# 04_ControllerStage_v1.net
KiCad netlist of a schematic drawn in EAGLE
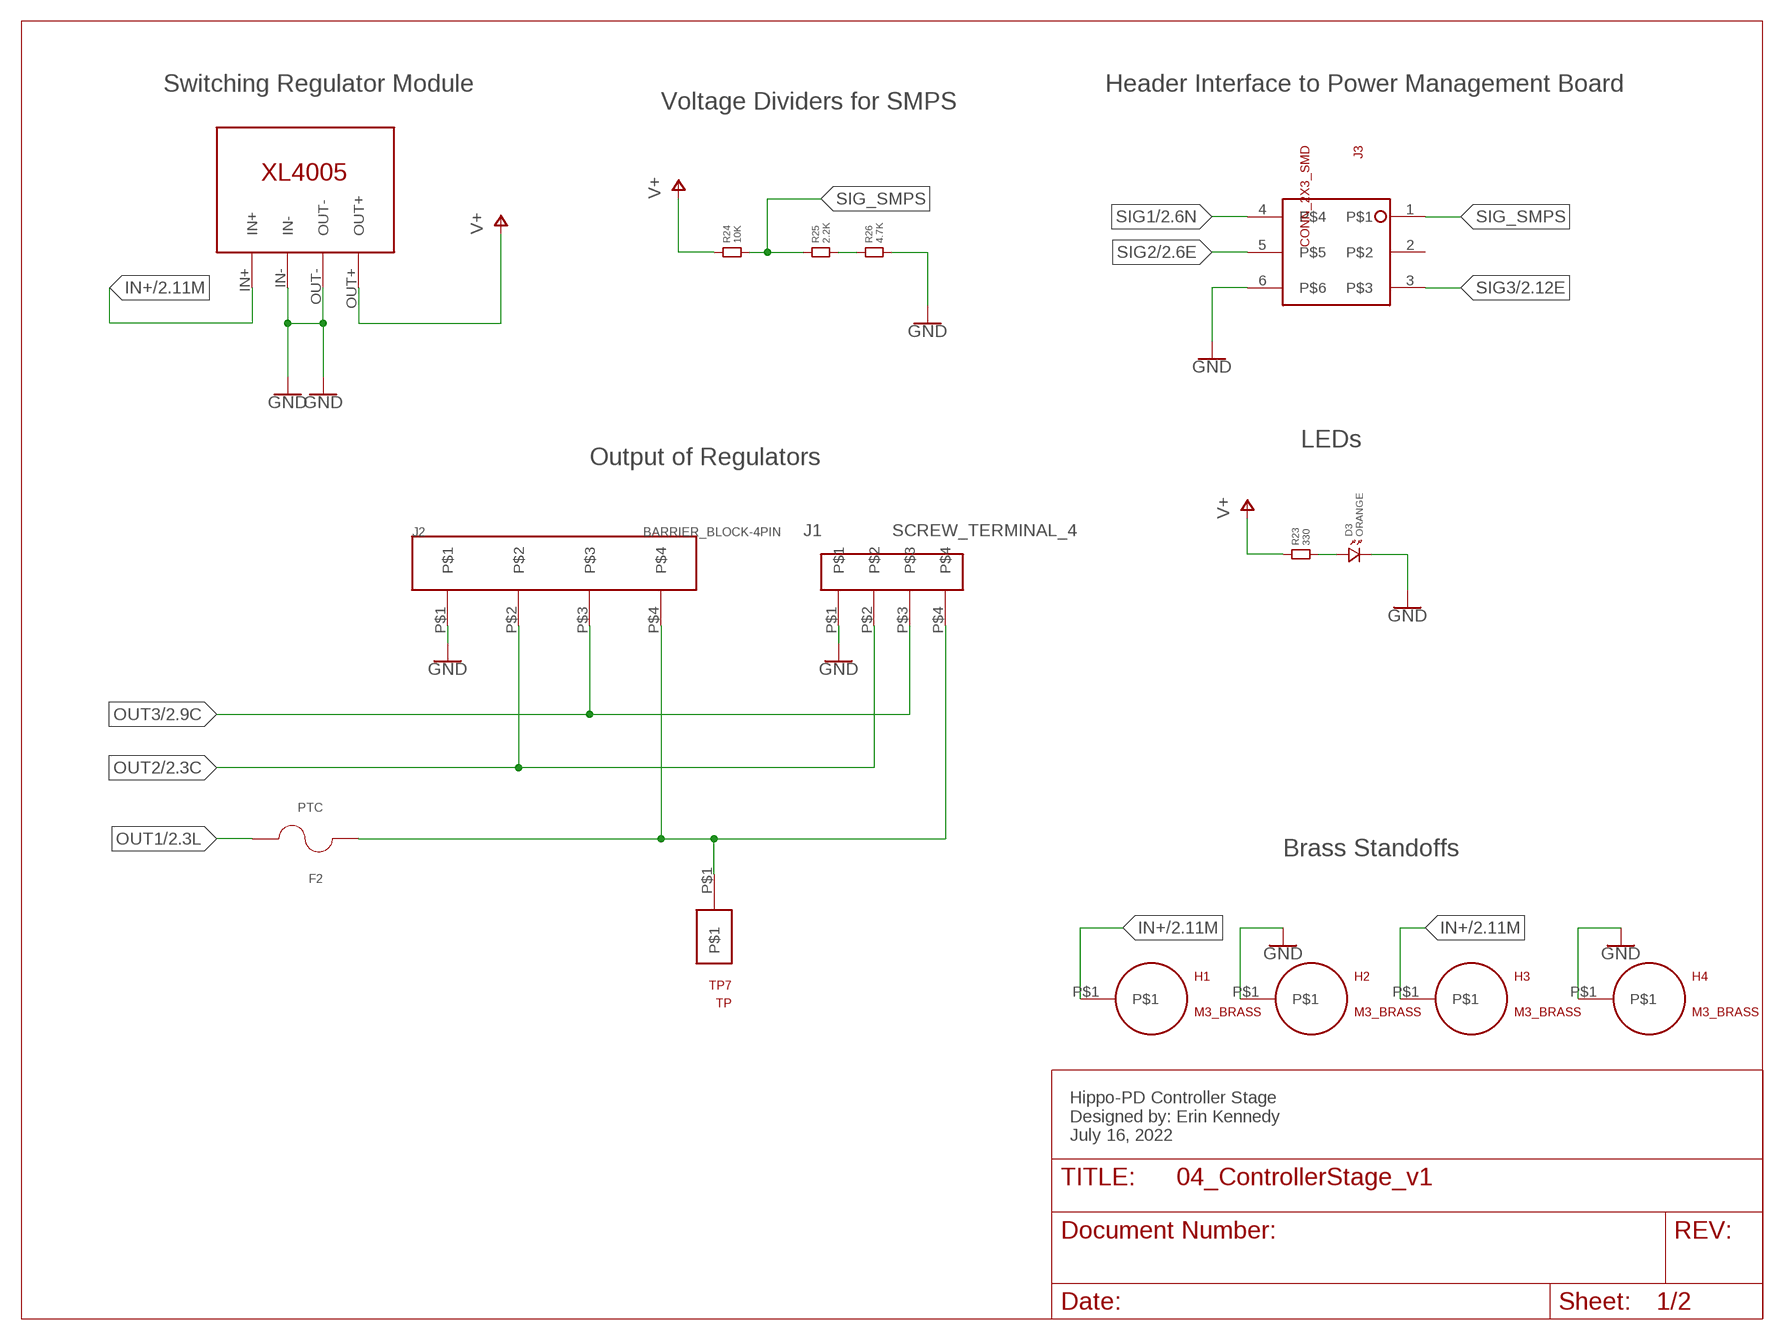
[diagram p0: schematic, sheet 1]
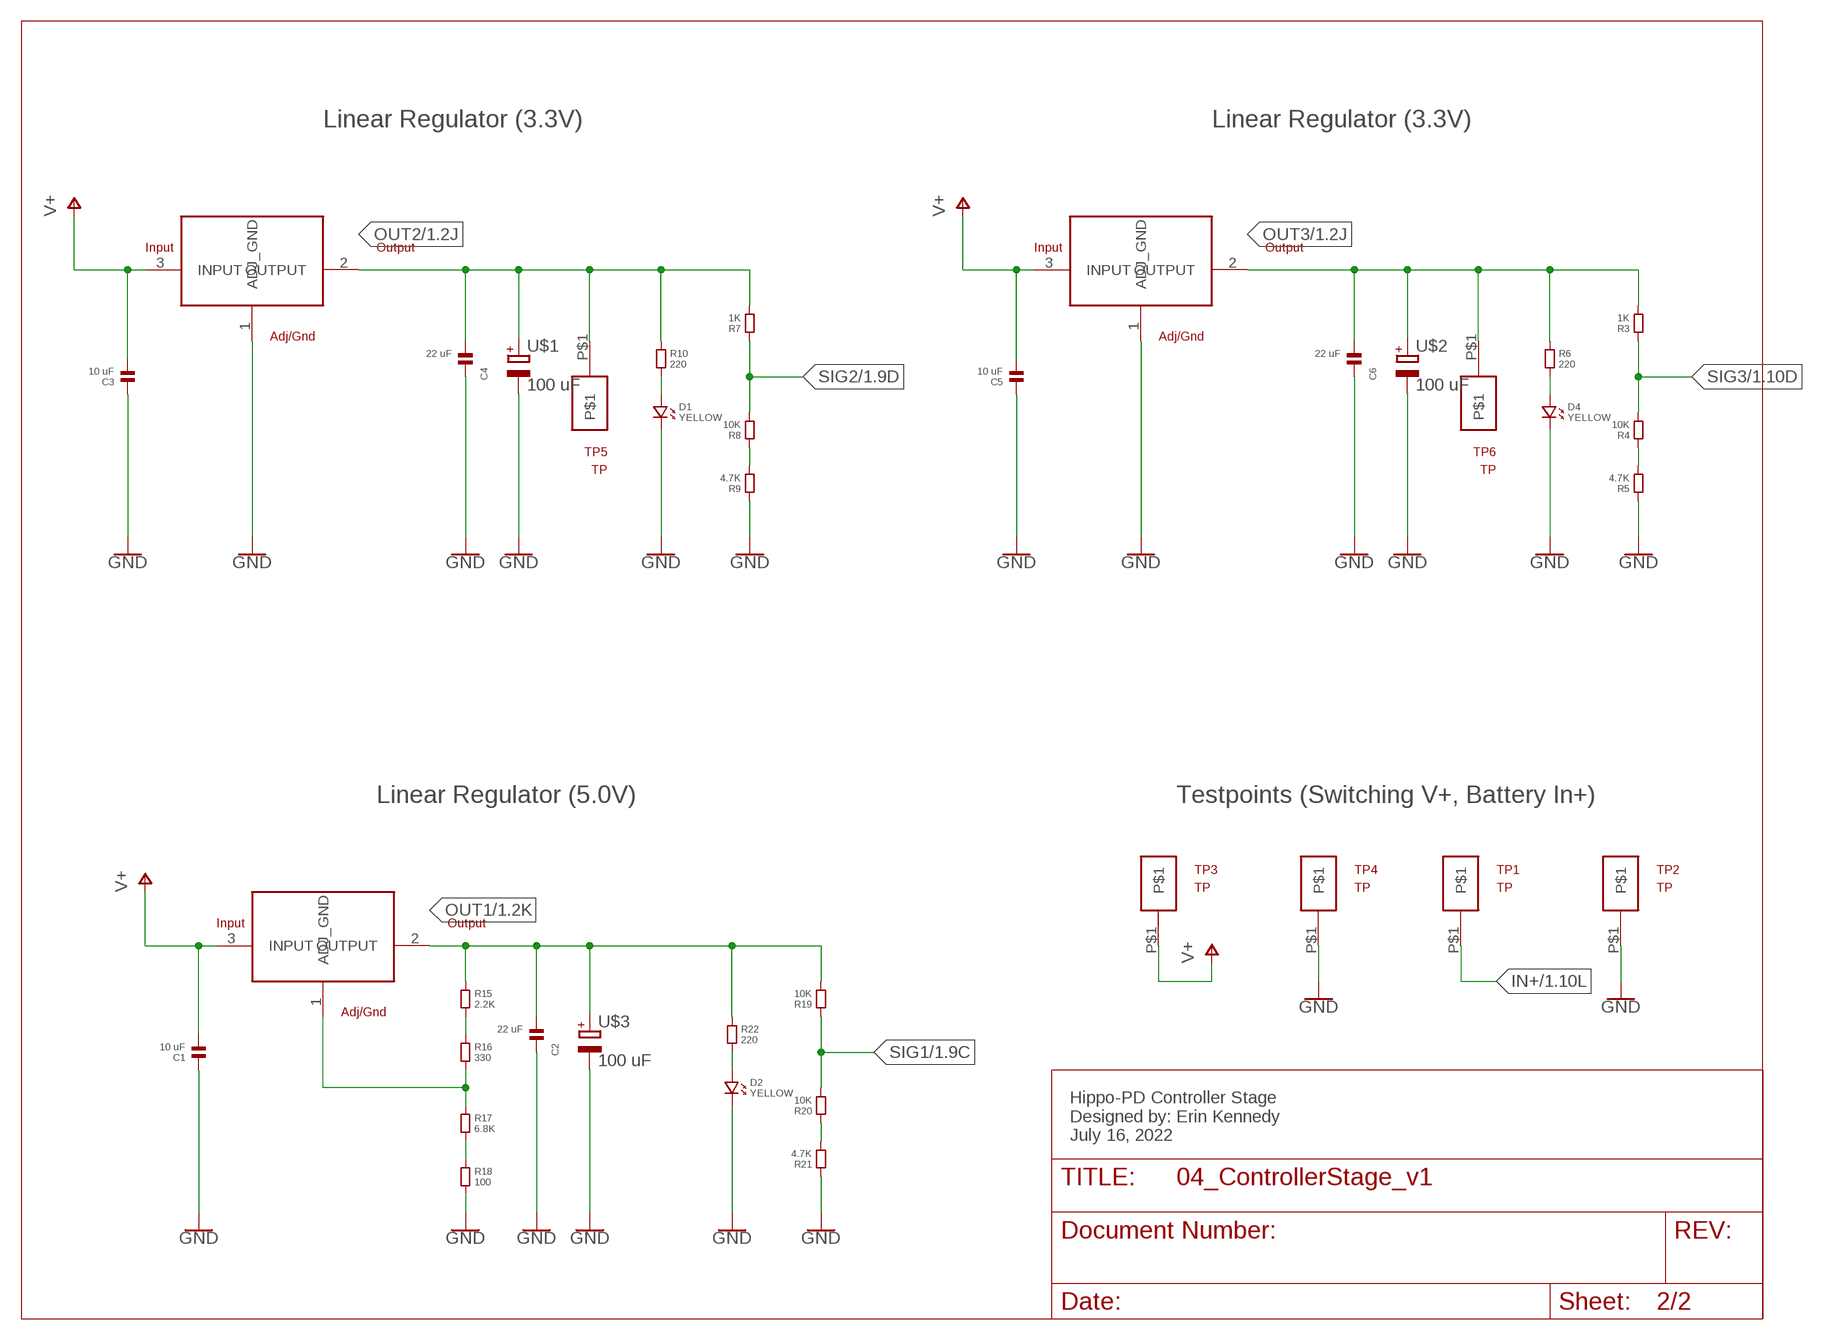
[diagram p1: schematic, sheet 2]

(export (version "E")
  (design (tool "Eeschema 10.0.6"))
  (components
    (comp (ref "C1")
      (value "10 uF")
      (footprint "eagle-import:1206")
      (libsource (lib "eagle-import") (part "CAPACITOR.1206"))
    )
    (comp (ref "C2")
      (value "22 uF")
      (footprint "eagle-import:1206")
      (libsource (lib "eagle-import") (part "CAPACITOR.1206"))
    )
    (comp (ref "C3")
      (value "10 uF")
      (footprint "eagle-import:1206")
      (libsource (lib "eagle-import") (part "CAPACITOR.1206"))
    )
    (comp (ref "C4")
      (value "22 uF")
      (footprint "eagle-import:1206")
      (libsource (lib "eagle-import") (part "CAPACITOR.1206"))
    )
    (comp (ref "C5")
      (value "10 uF")
      (footprint "eagle-import:1206")
      (libsource (lib "eagle-import") (part "CAPACITOR.1206"))
    )
    (comp (ref "C6")
      (value "22 uF")
      (footprint "eagle-import:1206")
      (libsource (lib "eagle-import") (part "CAPACITOR.1206"))
    )
    (comp (ref "D1")
      (value "YELLOW")
      (footprint "eagle-import:1206.LED")
      (libsource (lib "eagle-import") (part "LED.1206"))
    )
    (comp (ref "D2")
      (value "YELLOW")
      (footprint "eagle-import:1206.LED")
      (libsource (lib "eagle-import") (part "LED.1206"))
    )
    (comp (ref "D4")
      (value "YELLOW")
      (footprint "eagle-import:1206.LED")
      (libsource (lib "eagle-import") (part "LED.1206"))
    )
    (comp (ref "R1")
      (value "AZ1117CDAZ1117CD")
      (footprint "eagle-import:AZ1117CD")
      (libsource (lib "eagle-import") (part "AZ1117CDAZ1117CD"))
    )
    (comp (ref "R2")
      (value "AZ1117CDAZ1117CD")
      (footprint "eagle-import:AZ1117CD")
      (libsource (lib "eagle-import") (part "AZ1117CDAZ1117CD"))
    )
    (comp (ref "R3")
      (value "1K")
      (footprint "eagle-import:1206")
      (libsource (lib "eagle-import") (part "RESISTOR.1206"))
    )
    (comp (ref "R4")
      (value "10K")
      (footprint "eagle-import:1206")
      (libsource (lib "eagle-import") (part "RESISTOR.1206"))
    )
    (comp (ref "R5")
      (value "4.7K")
      (footprint "eagle-import:1206")
      (libsource (lib "eagle-import") (part "RESISTOR.1206"))
    )
    (comp (ref "R6")
      (value "220")
      (footprint "eagle-import:1206")
      (libsource (lib "eagle-import") (part "RESISTOR.1206"))
    )
    (comp (ref "R7")
      (value "1K")
      (footprint "eagle-import:1206")
      (libsource (lib "eagle-import") (part "RESISTOR.1206"))
    )
    (comp (ref "R8")
      (value "10K")
      (footprint "eagle-import:1206")
      (libsource (lib "eagle-import") (part "RESISTOR.1206"))
    )
    (comp (ref "R9")
      (value "4.7K")
      (footprint "eagle-import:1206")
      (libsource (lib "eagle-import") (part "RESISTOR.1206"))
    )
    (comp (ref "R10")
      (value "220")
      (footprint "eagle-import:1206")
      (libsource (lib "eagle-import") (part "RESISTOR.1206"))
    )
    (comp (ref "R14")
      (value "AZ1084C")
      (footprint "eagle-import:AZ1084C")
      (libsource (lib "eagle-import") (part "AZ1084C"))
    )
    (comp (ref "R15")
      (value "2.2K")
      (footprint "eagle-import:1206")
      (libsource (lib "eagle-import") (part "RESISTOR.1206"))
    )
    (comp (ref "R16")
      (value "330")
      (footprint "eagle-import:1206")
      (libsource (lib "eagle-import") (part "RESISTOR.1206"))
    )
    (comp (ref "R17")
      (value "6.8K")
      (footprint "eagle-import:1206")
      (libsource (lib "eagle-import") (part "RESISTOR.1206"))
    )
    (comp (ref "R18")
      (value "100")
      (footprint "eagle-import:1206")
      (libsource (lib "eagle-import") (part "RESISTOR.1206"))
    )
    (comp (ref "R19")
      (value "10K")
      (footprint "eagle-import:1206")
      (libsource (lib "eagle-import") (part "RESISTOR.1206"))
    )
    (comp (ref "R20")
      (value "10K")
      (footprint "eagle-import:1206")
      (libsource (lib "eagle-import") (part "RESISTOR.1206"))
    )
    (comp (ref "R21")
      (value "4.7K")
      (footprint "eagle-import:1206")
      (libsource (lib "eagle-import") (part "RESISTOR.1206"))
    )
    (comp (ref "R22")
      (value "220")
      (footprint "eagle-import:1206")
      (libsource (lib "eagle-import") (part "RESISTOR.1206"))
    )
    (comp (ref "TP1") (value "TP") (footprint "eagle-import:TP") (libsource (lib "eagle-import") (part "TP")))
    (comp (ref "TP2") (value "TP") (footprint "eagle-import:TP") (libsource (lib "eagle-import") (part "TP")))
    (comp (ref "TP3") (value "TP") (footprint "eagle-import:TP") (libsource (lib "eagle-import") (part "TP")))
    (comp (ref "TP4") (value "TP") (footprint "eagle-import:TP") (libsource (lib "eagle-import") (part "TP")))
    (comp (ref "TP5") (value "TP") (footprint "eagle-import:TP") (libsource (lib "eagle-import") (part "TP")))
    (comp (ref "TP6") (value "TP") (footprint "eagle-import:TP") (libsource (lib "eagle-import") (part "TP")))
    (comp (ref "U$1")
      (value "100 uF")
      (footprint "eagle-import:ELECTROLYTIC_CAP")
      (fields (field (name "MF") "Wurth Electronics") (field (name "MP") "865080545012"))
      (libsource (lib "eagle-import") (part "ELECTROLYTIC_CAP"))
    )
    (comp (ref "U$2")
      (value "100 uF")
      (footprint "eagle-import:ELECTROLYTIC_CAP")
      (fields (field (name "MF") "Wurth Electronics") (field (name "MP") "865080545012"))
      (libsource (lib "eagle-import") (part "ELECTROLYTIC_CAP"))
    )
    (comp (ref "U$3")
      (value "100 uF")
      (footprint "eagle-import:ELECTROLYTIC_CAP")
      (fields (field (name "MF") "Wurth Electronics") (field (name "MP") "865080545012"))
      (libsource (lib "eagle-import") (part "ELECTROLYTIC_CAP"))
    )
    (comp (ref "D3")
      (value "ORANGE")
      (footprint "eagle-import:1206.LED")
      (libsource (lib "eagle-import") (part "LED.1206"))
    )
    (comp (ref "F2")
      (value "PTC")
      (footprint "eagle-import:PTC")
      (fields (field (name "MF") "Bel Fuse") (field (name "MP") "0ZCF0075AF2C"))
      (libsource (lib "eagle-import") (part "PTC"))
    )
    (comp (ref "H1")
      (value "M3_BRASS")
      (footprint "eagle-import:M3_BRASS")
      (libsource (lib "eagle-import") (part "M3_BRASS"))
    )
    (comp (ref "H2")
      (value "M3_BRASS")
      (footprint "eagle-import:M3_BRASS")
      (libsource (lib "eagle-import") (part "M3_BRASS"))
    )
    (comp (ref "H3")
      (value "M3_BRASS")
      (footprint "eagle-import:M3_BRASS")
      (libsource (lib "eagle-import") (part "M3_BRASS"))
    )
    (comp (ref "H4")
      (value "M3_BRASS")
      (footprint "eagle-import:M3_BRASS")
      (libsource (lib "eagle-import") (part "M3_BRASS"))
    )
    (comp (ref "J1")
      (value "SCREW_TERMINAL_4")
      (footprint "eagle-import:SCREW_TERM_4")
      (libsource (lib "eagle-import") (part "SCREW_TERMINAL_4"))
    )
    (comp (ref "J2")
      (value "BARRIER_BLOCK-4PIN")
      (footprint "eagle-import:BARRIERBLOCK-4PIN")
      (libsource (lib "eagle-import") (part "BARRIER_BLOCK-4PIN"))
    )
    (comp (ref "J3")
      (value "CONN_2X3_SMD")
      (footprint "eagle-import:2X3_SMD_CONNECTOR")
      (libsource (lib "eagle-import") (part "CONN_2X3_SMD"))
    )
    (comp (ref "R23")
      (value "330")
      (footprint "eagle-import:1206")
      (libsource (lib "eagle-import") (part "RESISTOR.1206"))
    )
    (comp (ref "R24")
      (value "10K")
      (footprint "eagle-import:1206")
      (libsource (lib "eagle-import") (part "RESISTOR.1206"))
    )
    (comp (ref "R25")
      (value "2.2K")
      (footprint "eagle-import:1206")
      (libsource (lib "eagle-import") (part "RESISTOR.1206"))
    )
    (comp (ref "R26")
      (value "4.7K")
      (footprint "eagle-import:1206")
      (libsource (lib "eagle-import") (part "RESISTOR.1206"))
    )
    (comp (ref "TP7") (value "TP") (footprint "eagle-import:TP") (libsource (lib "eagle-import") (part "TP")))
    (comp (ref "U1")
      (value "XL4005-DEV")
      (footprint "eagle-import:XL4005-DEV")
      (libsource (lib "eagle-import") (part "XL4005-DEV"))
    )
  )
  (nets
    (net (code "1") (name "GND") (class "Default")
      (node (ref "C1") (pin "1") (pinfunction "1_1") (pintype "bidirectional"))
      (node (ref "C2") (pin "1") (pinfunction "1_1") (pintype "bidirectional"))
      (node (ref "C3") (pin "1") (pinfunction "1_1") (pintype "bidirectional"))
      (node (ref "C4") (pin "1") (pinfunction "1_1") (pintype "bidirectional"))
      (node (ref "C5") (pin "1") (pinfunction "1_1") (pintype "bidirectional"))
      (node (ref "C6") (pin "1") (pinfunction "1_1") (pintype "bidirectional"))
      (node (ref "D1") (pin "P$2") (pinfunction "2_P$2") (pintype "bidirectional"))
      (node (ref "D2") (pin "P$2") (pinfunction "2_P$2") (pintype "bidirectional"))
      (node (ref "D3") (pin "P$2") (pinfunction "2_P$2") (pintype "bidirectional"))
      (node (ref "D4") (pin "P$2") (pinfunction "2_P$2") (pintype "bidirectional"))
      (node (ref "H2") (pin "P$1") (pinfunction "P$1_P$1") (pintype "bidirectional"))
      (node (ref "H4") (pin "P$1") (pinfunction "P$1_P$1") (pintype "bidirectional"))
      (node (ref "J1") (pin "P$1") (pinfunction "P$1_P$1") (pintype "bidirectional"))
      (node (ref "J2") (pin "P$1") (pinfunction "P$1_P$1") (pintype "bidirectional"))
      (node (ref "J3") (pin "6") (pinfunction "P$6_6") (pintype "bidirectional"))
      (node (ref "R1") (pin "1") (pinfunction "ADJ_GND_1") (pintype "bidirectional"))
      (node (ref "R18") (pin "2") (pinfunction "2_2") (pintype "bidirectional"))
      (node (ref "R2") (pin "1") (pinfunction "ADJ_GND_1") (pintype "bidirectional"))
      (node (ref "R21") (pin "1") (pinfunction "1_1") (pintype "bidirectional"))
      (node (ref "R26") (pin "2") (pinfunction "2_2") (pintype "bidirectional"))
      (node (ref "R5") (pin "1") (pinfunction "1_1") (pintype "bidirectional"))
      (node (ref "R9") (pin "1") (pinfunction "1_1") (pintype "bidirectional"))
      (node (ref "TP2") (pin "P$1") (pinfunction "P$1_P$1") (pintype "bidirectional"))
      (node (ref "TP4") (pin "P$1") (pinfunction "P$1_P$1") (pintype "bidirectional"))
      (node (ref "U$1") (pin "-") (pinfunction "-_-") (pintype "passive"))
      (node (ref "U$2") (pin "-") (pinfunction "-_-") (pintype "passive"))
      (node (ref "U$3") (pin "-") (pinfunction "-_-") (pintype "passive"))
      (node (ref "U1") (pin "IN-") (pinfunction "IN-_IN-") (pintype "bidirectional"))
      (node (ref "U1") (pin "OUT-") (pinfunction "OUT-_OUT-") (pintype "bidirectional"))
    )
    (net (code "2") (name "IN+") (class "Default")
      (node (ref "H1") (pin "P$1") (pinfunction "P$1_P$1") (pintype "bidirectional"))
      (node (ref "H3") (pin "P$1") (pinfunction "P$1_P$1") (pintype "bidirectional"))
      (node (ref "TP1") (pin "P$1") (pinfunction "P$1_P$1") (pintype "bidirectional"))
      (node (ref "U1") (pin "IN+") (pinfunction "IN+_IN+") (pintype "bidirectional"))
    )
    (net (code "3") (name "Net-(D1-1)") (class "Default")
      (node (ref "D1") (pin "P$1") (pinfunction "1_P$1") (pintype "bidirectional"))
      (node (ref "R10") (pin "2") (pinfunction "2_2") (pintype "bidirectional"))
    )
    (net (code "4") (name "Net-(D2-1)") (class "Default")
      (node (ref "D2") (pin "P$1") (pinfunction "1_P$1") (pintype "bidirectional"))
      (node (ref "R22") (pin "2") (pinfunction "2_2") (pintype "bidirectional"))
    )
    (net (code "5") (name "Net-(D3-1)") (class "Default")
      (node (ref "D3") (pin "P$1") (pinfunction "1_P$1") (pintype "bidirectional"))
      (node (ref "R23") (pin "2") (pinfunction "2_2") (pintype "bidirectional"))
    )
    (net (code "6") (name "Net-(D4-1)") (class "Default")
      (node (ref "D4") (pin "P$1") (pinfunction "1_P$1") (pintype "bidirectional"))
      (node (ref "R6") (pin "2") (pinfunction "2_2") (pintype "bidirectional"))
    )
    (net (code "7") (name "Net-(F2-Pad1)") (class "Default")
      (node (ref "F2") (pin "1") (pinfunction "1_1") (pintype "passive"))
      (node (ref "J1") (pin "P$4") (pinfunction "P$4_P$4") (pintype "bidirectional"))
      (node (ref "J2") (pin "P$4") (pinfunction "P$4_P$4") (pintype "bidirectional"))
      (node (ref "TP7") (pin "P$1") (pinfunction "P$1_P$1") (pintype "bidirectional"))
    )
    (net (code "8") (name "Net-(R4-Pad1)") (class "Default")
      (node (ref "R4") (pin "1") (pinfunction "1_1") (pintype "bidirectional"))
      (node (ref "R5") (pin "2") (pinfunction "2_2") (pintype "bidirectional"))
    )
    (net (code "9") (name "Net-(R8-Pad1)") (class "Default")
      (node (ref "R8") (pin "1") (pinfunction "1_1") (pintype "bidirectional"))
      (node (ref "R9") (pin "2") (pinfunction "2_2") (pintype "bidirectional"))
    )
    (net (code "10") (name "Net-(R14-ADJ_GND)") (class "Default")
      (node (ref "R14") (pin "1") (pinfunction "ADJ_GND_1") (pintype "bidirectional"))
      (node (ref "R16") (pin "2") (pinfunction "2_2") (pintype "bidirectional"))
      (node (ref "R17") (pin "1") (pinfunction "1_1") (pintype "bidirectional"))
    )
    (net (code "11") (name "Net-(R15-Pad2)") (class "Default")
      (node (ref "R15") (pin "2") (pinfunction "2_2") (pintype "bidirectional"))
      (node (ref "R16") (pin "1") (pinfunction "1_1") (pintype "bidirectional"))
    )
    (net (code "12") (name "Net-(R17-Pad2)") (class "Default")
      (node (ref "R17") (pin "2") (pinfunction "2_2") (pintype "bidirectional"))
      (node (ref "R18") (pin "1") (pinfunction "1_1") (pintype "bidirectional"))
    )
    (net (code "13") (name "Net-(R20-Pad1)") (class "Default")
      (node (ref "R20") (pin "1") (pinfunction "1_1") (pintype "bidirectional"))
      (node (ref "R21") (pin "2") (pinfunction "2_2") (pintype "bidirectional"))
    )
    (net (code "14") (name "Net-(R25-Pad2)") (class "Default")
      (node (ref "R25") (pin "2") (pinfunction "2_2") (pintype "bidirectional"))
      (node (ref "R26") (pin "1") (pinfunction "1_1") (pintype "bidirectional"))
    )
    (net (code "15") (name "OUT1") (class "Default")
      (node (ref "C2") (pin "2") (pinfunction "2_2") (pintype "bidirectional"))
      (node (ref "F2") (pin "2") (pinfunction "2_2") (pintype "passive"))
      (node (ref "R14") (pin "2") (pinfunction "OUTPUT_2") (pintype "bidirectional"))
      (node (ref "R15") (pin "1") (pinfunction "1_1") (pintype "bidirectional"))
      (node (ref "R19") (pin "2") (pinfunction "2_2") (pintype "bidirectional"))
      (node (ref "R22") (pin "1") (pinfunction "1_1") (pintype "bidirectional"))
      (node (ref "U$3") (pin "+") (pinfunction "+_+") (pintype "passive"))
    )
    (net (code "16") (name "OUT2") (class "Default")
      (node (ref "C4") (pin "2") (pinfunction "2_2") (pintype "bidirectional"))
      (node (ref "J1") (pin "P$2") (pinfunction "P$2_P$2") (pintype "bidirectional"))
      (node (ref "J2") (pin "P$2") (pinfunction "P$2_P$2") (pintype "bidirectional"))
      (node (ref "R1") (pin "2") (pinfunction "OUTPUT_2") (pintype "bidirectional"))
      (node (ref "R10") (pin "1") (pinfunction "1_1") (pintype "bidirectional"))
      (node (ref "R7") (pin "2") (pinfunction "2_2") (pintype "bidirectional"))
      (node (ref "TP5") (pin "P$1") (pinfunction "P$1_P$1") (pintype "bidirectional"))
      (node (ref "U$1") (pin "+") (pinfunction "+_+") (pintype "passive"))
    )
    (net (code "17") (name "OUT3") (class "Default")
      (node (ref "C6") (pin "2") (pinfunction "2_2") (pintype "bidirectional"))
      (node (ref "J1") (pin "P$3") (pinfunction "P$3_P$3") (pintype "bidirectional"))
      (node (ref "J2") (pin "P$3") (pinfunction "P$3_P$3") (pintype "bidirectional"))
      (node (ref "R2") (pin "2") (pinfunction "OUTPUT_2") (pintype "bidirectional"))
      (node (ref "R3") (pin "2") (pinfunction "2_2") (pintype "bidirectional"))
      (node (ref "R6") (pin "1") (pinfunction "1_1") (pintype "bidirectional"))
      (node (ref "TP6") (pin "P$1") (pinfunction "P$1_P$1") (pintype "bidirectional"))
      (node (ref "U$2") (pin "+") (pinfunction "+_+") (pintype "passive"))
    )
    (net (code "18") (name "SIG1") (class "Default")
      (node (ref "J3") (pin "4") (pinfunction "P$4_4") (pintype "bidirectional"))
      (node (ref "R19") (pin "1") (pinfunction "1_1") (pintype "bidirectional"))
      (node (ref "R20") (pin "2") (pinfunction "2_2") (pintype "bidirectional"))
    )
    (net (code "19") (name "SIG2") (class "Default")
      (node (ref "J3") (pin "5") (pinfunction "P$5_5") (pintype "bidirectional"))
      (node (ref "R7") (pin "1") (pinfunction "1_1") (pintype "bidirectional"))
      (node (ref "R8") (pin "2") (pinfunction "2_2") (pintype "bidirectional"))
    )
    (net (code "20") (name "SIG3") (class "Default")
      (node (ref "J3") (pin "3") (pinfunction "P$3_3") (pintype "bidirectional"))
      (node (ref "R3") (pin "1") (pinfunction "1_1") (pintype "bidirectional"))
      (node (ref "R4") (pin "2") (pinfunction "2_2") (pintype "bidirectional"))
    )
    (net (code "21") (name "SIG_SMPS") (class "Default")
      (node (ref "J3") (pin "1") (pinfunction "P$1_1") (pintype "bidirectional"))
      (node (ref "R24") (pin "2") (pinfunction "2_2") (pintype "bidirectional"))
      (node (ref "R25") (pin "1") (pinfunction "1_1") (pintype "bidirectional"))
    )
    (net (code "22") (name "V+") (class "Default")
      (node (ref "C1") (pin "2") (pinfunction "2_2") (pintype "bidirectional"))
      (node (ref "C3") (pin "2") (pinfunction "2_2") (pintype "bidirectional"))
      (node (ref "C5") (pin "2") (pinfunction "2_2") (pintype "bidirectional"))
      (node (ref "R1") (pin "3") (pinfunction "INPUT_3") (pintype "bidirectional"))
      (node (ref "R14") (pin "3") (pinfunction "INPUT_3") (pintype "bidirectional"))
      (node (ref "R2") (pin "3") (pinfunction "INPUT_3") (pintype "bidirectional"))
      (node (ref "R23") (pin "1") (pinfunction "1_1") (pintype "bidirectional"))
      (node (ref "R24") (pin "1") (pinfunction "1_1") (pintype "bidirectional"))
      (node (ref "TP3") (pin "P$1") (pinfunction "P$1_P$1") (pintype "bidirectional"))
      (node (ref "U1") (pin "OUT+") (pinfunction "OUT+_OUT+") (pintype "bidirectional"))
    )
    (net (code "23") (name "unconnected-(J3-P$2-Pad2)") (class "Default")
      (node (ref "J3") (pin "2") (pinfunction "P$2_2") (pintype "bidirectional"))
    )
  )
)
